# PCI_short_card_universal_-_32_BIT-2.net
KiCad netlist of a schematic drawn in Altium Designer
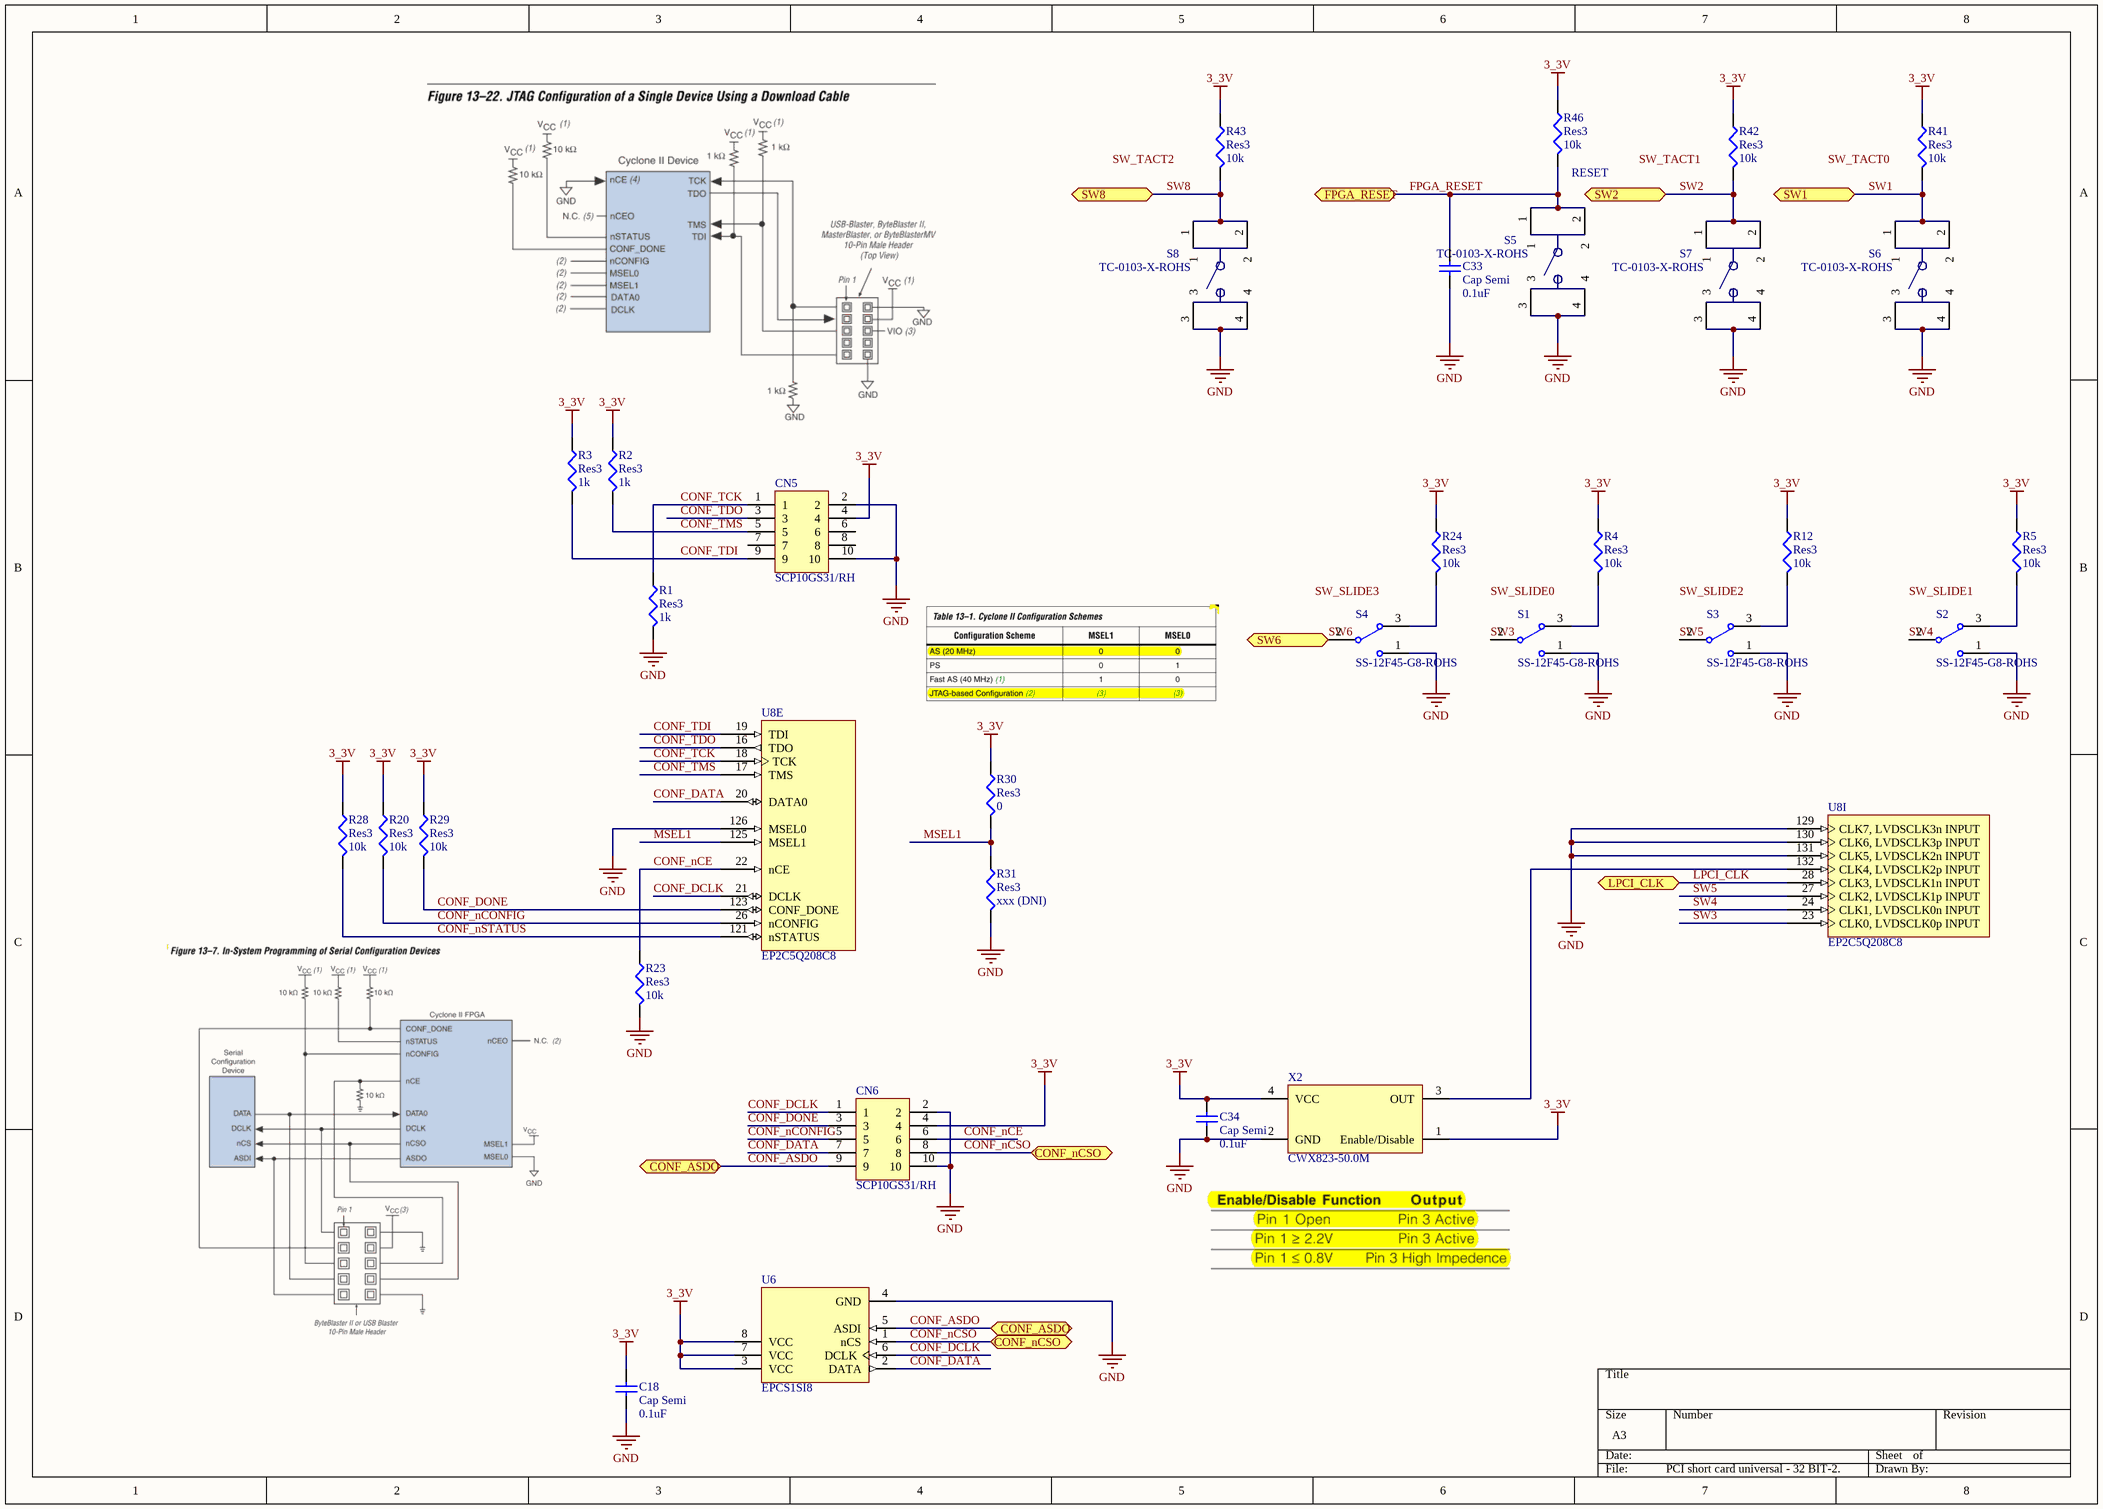
[diagram p0: PCI short card universal - 32 BIT-2.schdoc]

(export (version "E")
  (design (tool "Eeschema 10.0.6"))
  (components
    (comp (ref "C18")
      (value "Cap Semi")
      (footprint "RESC1608N")
      (description "Capacitor (Semiconductor SIM Model)")
      (fields (field (name "ALTIUM_VALUE") "0.1uF") (field (name "PUBLISHER") "Altium Limited"))
      (libsource (lib "Miscellaneous Devices") (part "Cap Semi"))
    )
    (comp (ref "C33")
      (value "Cap Semi")
      (footprint "PcbLib2:RESC1608N")
      (description "Capacitor (Semiconductor SIM Model)")
      (fields (field (name "ALTIUM_VALUE") "0.1uF") (field (name "PUBLISHER") "Altium Limited"))
      (libsource (lib "Miscellaneous Devices") (part "Cap Semi"))
    )
    (comp (ref "C34")
      (value "Cap Semi")
      (footprint "RESC1608N")
      (description "Capacitor (Semiconductor SIM Model)")
      (fields (field (name "ALTIUM_VALUE") "0.1uF") (field (name "PUBLISHER") "Altium Limited"))
      (libsource (lib "Miscellaneous Devices") (part "Cap Semi"))
    )
    (comp (ref "CN5")
      (value "SCP10GS31/RH")
      (footprint "SCP10GS31/RH")
      (description "GTK")
      (libsource (lib "Schlib1") (part "SCP10GS31/RH"))
    )
    (comp (ref "CN6")
      (value "SCP10GS31/RH")
      (footprint "SCP10GS31/RH")
      (libsource (lib "Schlib1") (part "SCP10GS31/RH"))
    )
    (comp (ref "R1")
      (value "Res3")
      (footprint "RESC1608N")
      (description "Resistor")
      (fields (field (name "ALTIUM_VALUE") "1k") (field (name "PUBLISHER") "Altium Limited"))
      (libsource (lib "Miscellaneous Devices") (part "Res3"))
    )
    (comp (ref "R2")
      (value "Res3")
      (footprint "RESC1608N")
      (description "Resistor")
      (fields (field (name "ALTIUM_VALUE") "1k") (field (name "PUBLISHER") "Altium Limited"))
      (libsource (lib "Miscellaneous Devices") (part "Res3"))
    )
    (comp (ref "R3")
      (value "Res3")
      (footprint "RESC1608N")
      (description "Resistor")
      (fields (field (name "ALTIUM_VALUE") "1k") (field (name "PUBLISHER") "Altium Limited"))
      (libsource (lib "Miscellaneous Devices") (part "Res3"))
    )
    (comp (ref "R4")
      (value "Res3")
      (footprint "PcbLib2:RESC1608N")
      (description "Resistor")
      (fields (field (name "ALTIUM_VALUE") "10k") (field (name "PUBLISHER") "Altium Limited"))
      (libsource (lib "Miscellaneous Devices") (part "Res3"))
    )
    (comp (ref "R5")
      (value "Res3")
      (footprint "RESC1608N")
      (description "Resistor")
      (fields (field (name "ALTIUM_VALUE") "10k") (field (name "PUBLISHER") "Altium Limited"))
      (libsource (lib "Miscellaneous Devices") (part "Res3"))
    )
    (comp (ref "R12")
      (value "Res3")
      (footprint "PcbLib2:RESC1608N")
      (description "Resistor")
      (fields (field (name "ALTIUM_VALUE") "10k") (field (name "PUBLISHER") "Altium Limited"))
      (libsource (lib "Miscellaneous Devices") (part "Res3"))
    )
    (comp (ref "R20")
      (value "Res3")
      (footprint "RESC1608N")
      (description "Resistor")
      (fields (field (name "ALTIUM_VALUE") "10k") (field (name "PUBLISHER") "Altium Limited"))
      (libsource (lib "Miscellaneous Devices") (part "Res3"))
    )
    (comp (ref "R23")
      (value "Res3")
      (footprint "RESC1608N")
      (description "Resistor")
      (fields (field (name "ALTIUM_VALUE") "10k") (field (name "PUBLISHER") "Altium Limited"))
      (libsource (lib "Miscellaneous Devices") (part "Res3"))
    )
    (comp (ref "R24")
      (value "Res3")
      (footprint "PcbLib2:RESC1608N")
      (description "Resistor")
      (fields (field (name "ALTIUM_VALUE") "10k") (field (name "PUBLISHER") "Altium Limited"))
      (libsource (lib "Miscellaneous Devices") (part "Res3"))
    )
    (comp (ref "R28")
      (value "Res3")
      (footprint "RESC1608N")
      (description "Resistor")
      (fields (field (name "ALTIUM_VALUE") "10k") (field (name "PUBLISHER") "Altium Limited"))
      (libsource (lib "Miscellaneous Devices") (part "Res3"))
    )
    (comp (ref "R29")
      (value "Res3")
      (footprint "RESC1608N")
      (description "Resistor")
      (fields (field (name "ALTIUM_VALUE") "10k") (field (name "PUBLISHER") "Altium Limited"))
      (libsource (lib "Miscellaneous Devices") (part "Res3"))
    )
    (comp (ref "R30")
      (value "Res3")
      (footprint "RESC1608N")
      (description "Resistor")
      (fields (field (name "ALTIUM_VALUE") "0") (field (name "PUBLISHER") "Altium Limited"))
      (libsource (lib "Miscellaneous Devices") (part "Res3"))
    )
    (comp (ref "R31")
      (value "Res3")
      (footprint "RESC1608N")
      (description "Resistor")
      (fields (field (name "ALTIUM_VALUE") "xxx (DNI)") (field (name "PUBLISHER") "Altium Limited"))
      (libsource (lib "Miscellaneous Devices") (part "Res3"))
    )
    (comp (ref "R41")
      (value "Res3")
      (footprint "RESC1608N")
      (description "Resistor")
      (fields (field (name "ALTIUM_VALUE") "10k") (field (name "PUBLISHER") "Altium Limited"))
      (libsource (lib "Miscellaneous Devices") (part "Res3"))
    )
    (comp (ref "R42")
      (value "Res3")
      (footprint "RESC1608N")
      (description "Resistor")
      (fields (field (name "ALTIUM_VALUE") "10k") (field (name "PUBLISHER") "Altium Limited"))
      (libsource (lib "Miscellaneous Devices") (part "Res3"))
    )
    (comp (ref "R43")
      (value "Res3")
      (footprint "RESC1608N")
      (description "Resistor")
      (fields (field (name "ALTIUM_VALUE") "10k") (field (name "PUBLISHER") "Altium Limited"))
      (libsource (lib "Miscellaneous Devices") (part "Res3"))
    )
    (comp (ref "R46")
      (value "Res3")
      (footprint "RESC1608N")
      (description "Resistor")
      (fields (field (name "ALTIUM_VALUE") "10k") (field (name "PUBLISHER") "Altium Limited"))
      (libsource (lib "Miscellaneous Devices") (part "Res3"))
    )
    (comp (ref "S1")
      (value "SS-12F45-G8-ROHS")
      (footprint "SLIDE_SW_2TYPE")
      (description "WEALTH METAL")
      (fields (field (name "PUBLISHER") "Altium Limited"))
      (libsource (lib "Miscellaneous Devices") (part "SW-SPDT"))
    )
    (comp (ref "S2")
      (value "SS-12F45-G8-ROHS")
      (footprint "SLIDE_SW_2TYPE")
      (description "WEALTH METAL")
      (fields (field (name "PUBLISHER") "Altium Limited"))
      (libsource (lib "Miscellaneous Devices") (part "SW-SPDT"))
    )
    (comp (ref "S3")
      (value "SS-12F45-G8-ROHS")
      (footprint "SLIDE_SW_2TYPE")
      (description "WEALTH METAL")
      (fields (field (name "PUBLISHER") "Altium Limited"))
      (libsource (lib "Miscellaneous Devices") (part "SW-SPDT"))
    )
    (comp (ref "S4")
      (value "SS-12F45-G8-ROHS")
      (footprint "SLIDE_SW_2TYPE")
      (description "WEALTH METAL")
      (fields (field (name "PUBLISHER") "Altium Limited"))
      (libsource (lib "Miscellaneous Devices") (part "SW-SPDT"))
    )
    (comp (ref "S5")
      (value "TC-0103-X-ROHS")
      (footprint "TACK_SW 6x6mm")
      (description "WEALTH METAL")
      (libsource (lib "Schlib1") (part "TC-0103-X-ROHS"))
    )
    (comp (ref "S6")
      (value "TC-0103-X-ROHS")
      (footprint "TACK_SW 6x6mm")
      (description "WEALTH METAL")
      (libsource (lib "Schlib1") (part "TC-0103-X-ROHS"))
    )
    (comp (ref "S7")
      (value "TC-0103-X-ROHS")
      (footprint "TACK_SW 6x6mm")
      (description "WEALTH METAL")
      (libsource (lib "Schlib1") (part "TC-0103-X-ROHS"))
    )
    (comp (ref "S8")
      (value "TC-0103-X-ROHS")
      (footprint "TACK_SW 6x6mm")
      (description "WEALTH METAL")
      (libsource (lib "Schlib1") (part "TC-0103-X-ROHS"))
    )
    (comp (ref "U6")
      (value "EPCS1SI8")
      (footprint "SOIC8_L")
      (fields (field (name "PUBLISHER") "Altium Limited"))
      (libsource (lib "Altera EPCS Configuration Device") (part "EPCS1SI8"))
    )
    (comp (ref "U8")
      (value "EP2C5Q208C8")
      (footprint "PQFP208_N")
      (fields (field (name "PUBLISHER") "Altium Limited"))
      (libsource (lib "Altera Cyclone II") (part "EP2C5Q208C8"))
    )
    (comp (ref "X2")
      (value "CWX823-50.0M")
      (footprint "CWX823-50.0M")
      (description "CONNOR-WINFIELD")
      (libsource (lib "Schlib1") (part "CWX823-50.0M"))
    )
  )
  (nets
    (net (code "1") (name "/CONF_ASDO") (class "Default")
      (node (ref "CN6") (pin "9") (pinfunction "9_9") (pintype "passive"))
      (node (ref "U6") (pin "5") (pinfunction "ASDI_5") (pintype "input"))
    )
    (net (code "2") (name "/CONF_DATA") (class "Default")
      (node (ref "CN6") (pin "7") (pinfunction "7_7") (pintype "passive"))
      (node (ref "U6") (pin "2") (pinfunction "DATA_2") (pintype "output"))
      (node (ref "U8") (pin "20") (pinfunction "DATA0_20") (pintype "bidirectional"))
    )
    (net (code "3") (name "/CONF_DCLK") (class "Default")
      (node (ref "CN6") (pin "1") (pinfunction "1_1") (pintype "passive"))
      (node (ref "U6") (pin "6") (pinfunction "DCLK_6") (pintype "input"))
      (node (ref "U8") (pin "21") (pinfunction "DCLK_21") (pintype "bidirectional"))
    )
    (net (code "4") (name "/CONF_DONE") (class "Default")
      (node (ref "CN6") (pin "3") (pinfunction "3_3") (pintype "passive"))
      (node (ref "R29") (pin "2") (pinfunction "2_2") (pintype "passive"))
      (node (ref "U8") (pin "123") (pinfunction "CONF_DONE_123") (pintype "bidirectional"))
    )
    (net (code "5") (name "/CONF_TCK") (class "Default")
      (node (ref "CN5") (pin "1") (pinfunction "1_1") (pintype "passive"))
      (node (ref "R1") (pin "1") (pinfunction "1_1") (pintype "passive"))
      (node (ref "U8") (pin "18") (pinfunction "TCK_18") (pintype "input"))
    )
    (net (code "6") (name "/CONF_TDI") (class "Default")
      (node (ref "CN5") (pin "9") (pinfunction "9_9") (pintype "passive"))
      (node (ref "R3") (pin "2") (pinfunction "2_2") (pintype "passive"))
      (node (ref "U8") (pin "19") (pinfunction "TDI_19") (pintype "input"))
    )
    (net (code "7") (name "/CONF_TDO") (class "Default")
      (node (ref "CN5") (pin "3") (pinfunction "3_3") (pintype "passive"))
      (node (ref "U8") (pin "16") (pinfunction "TDO_16") (pintype "output"))
    )
    (net (code "8") (name "/CONF_TMS") (class "Default")
      (node (ref "CN5") (pin "5") (pinfunction "5_5") (pintype "passive"))
      (node (ref "R2") (pin "2") (pinfunction "2_2") (pintype "passive"))
      (node (ref "U8") (pin "17") (pinfunction "TMS_17") (pintype "input"))
    )
    (net (code "9") (name "/CONF_nCE") (class "Default")
      (node (ref "CN6") (pin "6") (pinfunction "6_6") (pintype "passive"))
      (node (ref "R23") (pin "1") (pinfunction "1_1") (pintype "passive"))
      (node (ref "U8") (pin "22") (pinfunction "nCE_22") (pintype "input"))
    )
    (net (code "10") (name "/CONF_nCONFIG") (class "Default")
      (node (ref "CN6") (pin "5") (pinfunction "5_5") (pintype "passive"))
      (node (ref "R20") (pin "2") (pinfunction "2_2") (pintype "passive"))
      (node (ref "U8") (pin "26") (pinfunction "nCONFIG_26") (pintype "input"))
    )
    (net (code "11") (name "/CONF_nCSO") (class "Default")
      (node (ref "CN6") (pin "8") (pinfunction "8_8") (pintype "passive"))
      (node (ref "U6") (pin "1") (pinfunction "nCS_1") (pintype "input"))
    )
    (net (code "12") (name "/CONF_nSTATUS") (class "Default")
      (node (ref "R28") (pin "2") (pinfunction "2_2") (pintype "passive"))
      (node (ref "U8") (pin "121") (pinfunction "nSTATUS_121") (pintype "bidirectional"))
    )
    (net (code "13") (name "/FPGA_RESET") (class "Default")
      (node (ref "C33") (pin "2") (pinfunction "2_2") (pintype "passive"))
      (node (ref "R46") (pin "2") (pinfunction "2_2") (pintype "passive"))
      (node (ref "S5") (pin "1") (pinfunction "1_1") (pintype "passive"))
      (node (ref "S5") (pin "2") (pinfunction "2_2") (pintype "passive"))
    )
    (net (code "14") (name "/LPCI_CLK") (class "Default")
      (node (ref "U8") (pin "28") (pinfunction "CLK3,_LVDSCLK1n_INPUT_28") (pintype "input"))
    )
    (net (code "15") (name "/MSEL1") (class "Default")
      (node (ref "R30") (pin "2") (pinfunction "2_2") (pintype "passive"))
      (node (ref "R31") (pin "1") (pinfunction "1_1") (pintype "passive"))
      (node (ref "U8") (pin "125") (pinfunction "MSEL1_125") (pintype "input"))
    )
    (net (code "16") (name "/SW1") (class "Default")
      (node (ref "R41") (pin "2") (pinfunction "2_2") (pintype "passive"))
      (node (ref "S6") (pin "1") (pinfunction "1_1") (pintype "passive"))
      (node (ref "S6") (pin "2") (pinfunction "2_2") (pintype "passive"))
    )
    (net (code "17") (name "/SW2") (class "Default")
      (node (ref "R42") (pin "2") (pinfunction "2_2") (pintype "passive"))
      (node (ref "S7") (pin "1") (pinfunction "1_1") (pintype "passive"))
      (node (ref "S7") (pin "2") (pinfunction "2_2") (pintype "passive"))
    )
    (net (code "18") (name "/SW3") (class "Default")
      (node (ref "S1") (pin "2") (pinfunction "2_2") (pintype "passive"))
      (node (ref "U8") (pin "23") (pinfunction "CLK0,_LVDSCLK0p_INPUT_23") (pintype "input"))
    )
    (net (code "19") (name "/SW4") (class "Default")
      (node (ref "S2") (pin "2") (pinfunction "2_2") (pintype "passive"))
      (node (ref "U8") (pin "24") (pinfunction "CLK1,_LVDSCLK0n_INPUT_24") (pintype "input"))
    )
    (net (code "20") (name "/SW5") (class "Default")
      (node (ref "S3") (pin "2") (pinfunction "2_2") (pintype "passive"))
      (node (ref "U8") (pin "27") (pinfunction "CLK2,_LVDSCLK1p_INPUT_27") (pintype "input"))
    )
    (net (code "21") (name "/SW6") (class "Default")
      (node (ref "S4") (pin "2") (pinfunction "2_2") (pintype "passive"))
    )
    (net (code "22") (name "/SW8") (class "Default")
      (node (ref "R43") (pin "2") (pinfunction "2_2") (pintype "passive"))
      (node (ref "S8") (pin "1") (pinfunction "1_1") (pintype "passive"))
      (node (ref "S8") (pin "2") (pinfunction "2_2") (pintype "passive"))
    )
    (net (code "30") (name "3_3V") (class "Default")
      (node (ref "C18") (pin "2") (pinfunction "2_2") (pintype "passive"))
      (node (ref "C34") (pin "2") (pinfunction "2_2") (pintype "passive"))
      (node (ref "CN5") (pin "4") (pinfunction "4_4") (pintype "passive"))
      (node (ref "CN6") (pin "4") (pinfunction "4_4") (pintype "passive"))
      (node (ref "R12") (pin "1") (pinfunction "1_1") (pintype "passive"))
      (node (ref "R2") (pin "1") (pinfunction "1_1") (pintype "passive"))
      (node (ref "R20") (pin "1") (pinfunction "1_1") (pintype "passive"))
      (node (ref "R24") (pin "1") (pinfunction "1_1") (pintype "passive"))
      (node (ref "R28") (pin "1") (pinfunction "1_1") (pintype "passive"))
      (node (ref "R29") (pin "1") (pinfunction "1_1") (pintype "passive"))
      (node (ref "R3") (pin "1") (pinfunction "1_1") (pintype "passive"))
      (node (ref "R30") (pin "1") (pinfunction "1_1") (pintype "passive"))
      (node (ref "R4") (pin "1") (pinfunction "1_1") (pintype "passive"))
      (node (ref "R41") (pin "1") (pinfunction "1_1") (pintype "passive"))
      (node (ref "R42") (pin "1") (pinfunction "1_1") (pintype "passive"))
      (node (ref "R43") (pin "1") (pinfunction "1_1") (pintype "passive"))
      (node (ref "R46") (pin "1") (pinfunction "1_1") (pintype "passive"))
      (node (ref "R5") (pin "1") (pinfunction "1_1") (pintype "passive"))
      (node (ref "U6") (pin "3") (pinfunction "VCC_3") (pintype "power_in"))
      (node (ref "U6") (pin "7") (pinfunction "VCC_7") (pintype "power_in"))
      (node (ref "U6") (pin "8") (pinfunction "VCC_8") (pintype "power_in"))
      (node (ref "X2") (pin "1") (pinfunction "Enable/Disable_1") (pintype "passive"))
      (node (ref "X2") (pin "4") (pinfunction "VCC_4") (pintype "passive"))
    )
    (net (code "31") (name "GND") (class "Default")
      (node (ref "C18") (pin "1") (pinfunction "1_1") (pintype "passive"))
      (node (ref "C33") (pin "1") (pinfunction "1_1") (pintype "passive"))
      (node (ref "C34") (pin "1") (pinfunction "1_1") (pintype "passive"))
      (node (ref "CN5") (pin "10") (pinfunction "10_10") (pintype "passive"))
      (node (ref "CN5") (pin "2") (pinfunction "2_2") (pintype "passive"))
      (node (ref "CN6") (pin "10") (pinfunction "10_10") (pintype "passive"))
      (node (ref "CN6") (pin "2") (pinfunction "2_2") (pintype "passive"))
      (node (ref "R1") (pin "2") (pinfunction "2_2") (pintype "passive"))
      (node (ref "R23") (pin "2") (pinfunction "2_2") (pintype "passive"))
      (node (ref "R31") (pin "2") (pinfunction "2_2") (pintype "passive"))
      (node (ref "S1") (pin "1") (pinfunction "1_1") (pintype "passive"))
      (node (ref "S2") (pin "1") (pinfunction "1_1") (pintype "passive"))
      (node (ref "S3") (pin "1") (pinfunction "1_1") (pintype "passive"))
      (node (ref "S4") (pin "1") (pinfunction "1_1") (pintype "passive"))
      (node (ref "S5") (pin "3") (pinfunction "3_3") (pintype "passive"))
      (node (ref "S5") (pin "4") (pinfunction "4_4") (pintype "passive"))
      (node (ref "S6") (pin "3") (pinfunction "3_3") (pintype "passive"))
      (node (ref "S6") (pin "4") (pinfunction "4_4") (pintype "passive"))
      (node (ref "S7") (pin "3") (pinfunction "3_3") (pintype "passive"))
      (node (ref "S7") (pin "4") (pinfunction "4_4") (pintype "passive"))
      (node (ref "S8") (pin "3") (pinfunction "3_3") (pintype "passive"))
      (node (ref "S8") (pin "4") (pinfunction "4_4") (pintype "passive"))
      (node (ref "U6") (pin "4") (pinfunction "GND_4") (pintype "power_in"))
      (node (ref "U8") (pin "126") (pinfunction "MSEL0_126") (pintype "input"))
      (node (ref "U8") (pin "129") (pinfunction "CLK7,_LVDSCLK3n_INPUT_129") (pintype "input"))
      (node (ref "U8") (pin "130") (pinfunction "CLK6,_LVDSCLK3p_INPUT_130") (pintype "input"))
      (node (ref "U8") (pin "131") (pinfunction "CLK5,_LVDSCLK2n_INPUT_131") (pintype "input"))
      (node (ref "X2") (pin "2") (pinfunction "GND_2") (pintype "passive"))
    )
    (net (code "32") (name "Net-(R4-Pad2)") (class "Default")
      (node (ref "R4") (pin "2") (pinfunction "2_2") (pintype "passive"))
      (node (ref "S1") (pin "3") (pinfunction "3_3") (pintype "passive"))
    )
    (net (code "33") (name "Net-(R5-Pad2)") (class "Default")
      (node (ref "R5") (pin "2") (pinfunction "2_2") (pintype "passive"))
      (node (ref "S2") (pin "3") (pinfunction "3_3") (pintype "passive"))
    )
    (net (code "34") (name "Net-(R12-Pad2)") (class "Default")
      (node (ref "R12") (pin "2") (pinfunction "2_2") (pintype "passive"))
      (node (ref "S3") (pin "3") (pinfunction "3_3") (pintype "passive"))
    )
    (net (code "35") (name "Net-(R24-Pad2)") (class "Default")
      (node (ref "R24") (pin "2") (pinfunction "2_2") (pintype "passive"))
      (node (ref "S4") (pin "3") (pinfunction "3_3") (pintype "passive"))
    )
    (net (code "36") (name "Net-(U8I-CLK4,_LVDSCLK2p_INPUT)") (class "Default")
      (node (ref "U8") (pin "132") (pinfunction "CLK4,_LVDSCLK2p_INPUT_132") (pintype "input"))
      (node (ref "X2") (pin "3") (pinfunction "OUT_3") (pintype "passive"))
    )
    (net (code "37") (name "unconnected-(CN5-Pad6)") (class "Default")
      (node (ref "CN5") (pin "6") (pinfunction "6_6") (pintype "passive"))
    )
    (net (code "38") (name "unconnected-(CN5-Pad7)") (class "Default")
      (node (ref "CN5") (pin "7") (pinfunction "7_7") (pintype "passive"))
    )
    (net (code "39") (name "unconnected-(CN5-Pad8)") (class "Default")
      (node (ref "CN5") (pin "8") (pinfunction "8_8") (pintype "passive"))
    )
  )
)
